# USBFTDI_I2C_V1.net
KiCad netlist of a schematic drawn in EAGLE
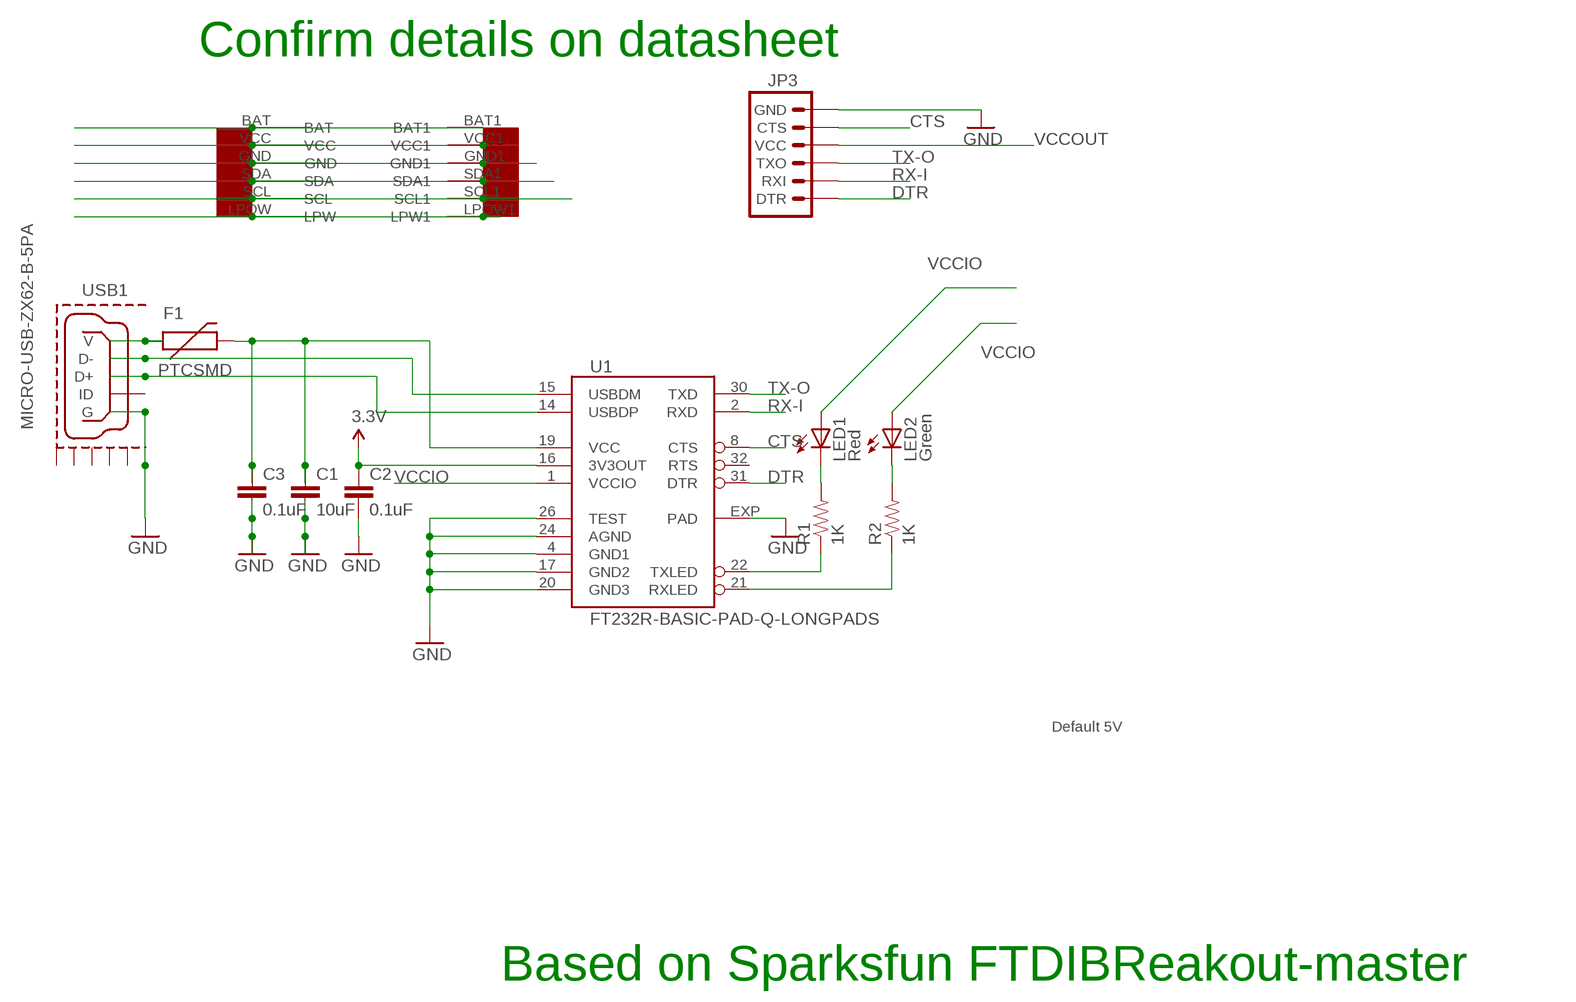
[diagram p0: schematic, sheet 1]

(export (version "E")
  (design (tool "Eeschema 10.0.6"))
  (components
    (comp (ref "C1")
      (value "10uF")
      (footprint "eagle-import:0402-CAP")
      (libsource (lib "eagle-import") (part "CAP-0402"))
    )
    (comp (ref "C2")
      (value "0.1uF")
      (footprint "eagle-import:0402-CAP")
      (libsource (lib "eagle-import") (part "CAP-0402"))
    )
    (comp (ref "C3")
      (value "0.1uF")
      (footprint "eagle-import:0402-CAP")
      (libsource (lib "eagle-import") (part "CAP-0402"))
    )
    (comp (ref "F1")
      (value "PTCSMD")
      (footprint "eagle-import:PTC-1206")
      (libsource (lib "eagle-import") (part "PTCSMD"))
    )
    (comp (ref "JP3")
      (value "ARDUINO_SERIAL_PROGRAMPTH")
      (footprint "eagle-import:1X06")
      (libsource (lib "eagle-import") (part "ARDUINO_SERIAL_PROGRAMPTH"))
    )
    (comp (ref "LED1")
      (value "Red")
      (footprint "eagle-import:LED-0603")
      (libsource (lib "eagle-import") (part "LED0603"))
    )
    (comp (ref "LED2")
      (value "Green")
      (footprint "eagle-import:LED-0603")
      (libsource (lib "eagle-import") (part "LED0603"))
    )
    (comp (ref "R1")
      (value "1K")
      (footprint "eagle-import:R0402")
      (libsource (lib "eagle-import") (part "RESISTOR-0402"))
    )
    (comp (ref "R2")
      (value "1K")
      (footprint "eagle-import:R0402")
      (libsource (lib "eagle-import") (part "RESISTOR-0402"))
    )
    (comp (ref "U$1")
      (value "EZ-I2CHEADERV1")
      (footprint "eagle-import:EZ-I2CHEADERV1")
      (libsource (lib "eagle-import") (part "EZ-I2CHEADERV1"))
    )
    (comp (ref "U1")
      (value "FT232R-BASIC-PAD-Q-LONGPADS")
      (footprint "eagle-import:QFN32-LONG")
      (libsource (lib "eagle-import") (part "FT232R-BASIC-PAD-Q-LONGPADS"))
    )
    (comp (ref "USB1")
      (value "MICRO-USB-ZX62-B-5PA")
      (footprint "eagle-import:ZX62-B-5PA")
      (libsource (lib "eagle-import") (part "MICRO-USB-ZX62-B-5PA"))
    )
  )
  (nets
    (net (code "1") (name "/CTS") (class "Default")
      (node (ref "JP3") (pin "5") (pinfunction "CTS_5") (pintype "passive"))
      (node (ref "U1") (pin "8") (pinfunction "CTS_8") (pintype "bidirectional"))
    )
    (net (code "2") (name "/DTR") (class "Default")
      (node (ref "JP3") (pin "1") (pinfunction "DTR_1") (pintype "passive"))
      (node (ref "U1") (pin "31") (pinfunction "DTR_31") (pintype "bidirectional"))
    )
    (net (code "3") (name "/GND1") (class "Default")
      (node (ref "USB1") (pin "GND@1") (pinfunction "GND1_GND@1") (pintype "power_in"))
    )
    (net (code "4") (name "/GND2") (class "Default")
      (node (ref "USB1") (pin "GND@2") (pinfunction "GND2_GND@2") (pintype "power_in"))
    )
    (net (code "5") (name "/GND3") (class "Default")
      (node (ref "USB1") (pin "GND@3") (pinfunction "GND3_GND@3") (pintype "power_in"))
    )
    (net (code "6") (name "/GND4") (class "Default")
      (node (ref "USB1") (pin "GND@4") (pinfunction "GND4_GND@4") (pintype "power_in"))
    )
    (net (code "7") (name "/GND5") (class "Default")
      (node (ref "USB1") (pin "GND@5") (pinfunction "GND5_GND@5") (pintype "power_in"))
    )
    (net (code "8") (name "/RX-I") (class "Default")
      (node (ref "JP3") (pin "2") (pinfunction "RXI_2") (pintype "passive"))
      (node (ref "U1") (pin "2") (pinfunction "RXD_2") (pintype "input"))
    )
    (net (code "9") (name "/TX-O") (class "Default")
      (node (ref "JP3") (pin "3") (pinfunction "TXO_3") (pintype "passive"))
      (node (ref "U1") (pin "30") (pinfunction "TXD_30") (pintype "output"))
    )
    (net (code "10") (name "/VCCIO") (class "Default")
      (node (ref "LED1") (pin "A") (pinfunction "A_A") (pintype "passive"))
      (node (ref "LED2") (pin "A") (pinfunction "A_A") (pintype "passive"))
      (node (ref "U1") (pin "1") (pinfunction "VCCIO_1") (pintype "power_in"))
    )
    (net (code "11") (name "/VCCOUT") (class "Default")
      (node (ref "JP3") (pin "4") (pinfunction "VCC_4") (pintype "passive"))
    )
    (net (code "12") (name "3.3V") (class "Default")
      (node (ref "C2") (pin "1") (pinfunction "1_1") (pintype "passive"))
      (node (ref "U$1") (pin "VCC") (pinfunction "VCC_VCC") (pintype "bidirectional"))
      (node (ref "U$1") (pin "VCC1") (pinfunction "VCC1_VCC1") (pintype "bidirectional"))
      (node (ref "U1") (pin "16") (pinfunction "3V3OUT_16") (pintype "output"))
    )
    (net (code "13") (name "GND") (class "Default")
      (node (ref "C1") (pin "2") (pinfunction "2_2") (pintype "passive"))
      (node (ref "C2") (pin "2") (pinfunction "2_2") (pintype "passive"))
      (node (ref "C3") (pin "2") (pinfunction "2_2") (pintype "passive"))
      (node (ref "JP3") (pin "6") (pinfunction "GND_6") (pintype "passive"))
      (node (ref "U$1") (pin "GND") (pinfunction "GND_GND") (pintype "bidirectional"))
      (node (ref "U$1") (pin "GND1") (pinfunction "GND1_GND1") (pintype "bidirectional"))
      (node (ref "U1") (pin "17") (pinfunction "GND2_17") (pintype "power_in"))
      (node (ref "U1") (pin "20") (pinfunction "GND3_20") (pintype "power_in"))
      (node (ref "U1") (pin "24") (pinfunction "AGND_24") (pintype "power_in"))
      (node (ref "U1") (pin "26") (pinfunction "TEST_26") (pintype "input"))
      (node (ref "U1") (pin "4") (pinfunction "GND1_4") (pintype "power_in"))
      (node (ref "U1") (pin "EXP") (pinfunction "PAD_EXP") (pintype "bidirectional"))
      (node (ref "USB1") (pin "5") (pinfunction "G_5") (pintype "input"))
      (node (ref "USB1") (pin "GND@6") (pinfunction "GND6_GND@6") (pintype "power_in"))
    )
    (net (code "14") (name "Net-(LED1-PadC)") (class "Default")
      (node (ref "LED1") (pin "C") (pinfunction "C_C") (pintype "passive"))
      (node (ref "R1") (pin "2") (pinfunction "2_2") (pintype "passive"))
    )
    (net (code "15") (name "Net-(LED2-PadC)") (class "Default")
      (node (ref "LED2") (pin "C") (pinfunction "C_C") (pintype "passive"))
      (node (ref "R2") (pin "2") (pinfunction "2_2") (pintype "passive"))
    )
    (net (code "16") (name "Net-(U$1-LPW)") (class "Default")
      (node (ref "U$1") (pin "LPOW") (pinfunction "LPW_LPOW") (pintype "bidirectional"))
      (node (ref "U$1") (pin "LPOW1") (pinfunction "LPW1_LPOW1") (pintype "bidirectional"))
    )
    (net (code "17") (name "Net-(U$1-PadBAT)") (class "Default")
      (node (ref "U$1") (pin "BAT") (pinfunction "BAT_BAT") (pintype "bidirectional"))
      (node (ref "U$1") (pin "BAT1") (pinfunction "BAT1_BAT1") (pintype "bidirectional"))
    )
    (net (code "18") (name "Net-(U$1-PadSCL)") (class "Default")
      (node (ref "U$1") (pin "SCL") (pinfunction "SCL_SCL") (pintype "bidirectional"))
      (node (ref "U$1") (pin "SCL1") (pinfunction "SCL1_SCL1") (pintype "bidirectional"))
    )
    (net (code "19") (name "Net-(U$1-PadSDA)") (class "Default")
      (node (ref "U$1") (pin "SDA") (pinfunction "SDA_SDA") (pintype "bidirectional"))
      (node (ref "U$1") (pin "SDA1") (pinfunction "SDA1_SDA1") (pintype "bidirectional"))
    )
    (net (code "20") (name "Net-(U1-RXLED)") (class "Default")
      (node (ref "R2") (pin "1") (pinfunction "1_1") (pintype "passive"))
      (node (ref "U1") (pin "21") (pinfunction "RXLED_21") (pintype "bidirectional"))
    )
    (net (code "21") (name "Net-(U1-TXLED)") (class "Default")
      (node (ref "R1") (pin "1") (pinfunction "1_1") (pintype "passive"))
      (node (ref "U1") (pin "22") (pinfunction "TXLED_22") (pintype "bidirectional"))
    )
    (net (code "22") (name "Net-(U1-USBDM)") (class "Default")
      (node (ref "U1") (pin "15") (pinfunction "USBDM_15") (pintype "bidirectional"))
      (node (ref "USB1") (pin "2") (pinfunction "D-_2") (pintype "input"))
    )
    (net (code "23") (name "Net-(U1-USBDP)") (class "Default")
      (node (ref "U1") (pin "14") (pinfunction "USBDP_14") (pintype "bidirectional"))
      (node (ref "USB1") (pin "3") (pinfunction "D+_3") (pintype "input"))
    )
    (net (code "24") (name "Net-(U1-VCC)") (class "Default")
      (node (ref "C1") (pin "1") (pinfunction "1_1") (pintype "passive"))
      (node (ref "C3") (pin "1") (pinfunction "1_1") (pintype "passive"))
      (node (ref "F1") (pin "2") (pinfunction "2_2") (pintype "bidirectional"))
      (node (ref "U1") (pin "19") (pinfunction "VCC_19") (pintype "power_in"))
    )
    (net (code "25") (name "Net-(USB1-V)") (class "Default")
      (node (ref "F1") (pin "1") (pinfunction "1_1") (pintype "bidirectional"))
      (node (ref "USB1") (pin "1") (pinfunction "V_1") (pintype "input"))
    )
    (net (code "26") (name "unconnected-(U1-RTS-Pad32)") (class "Default")
      (node (ref "U1") (pin "32") (pinfunction "RTS_32") (pintype "bidirectional"))
    )
    (net (code "27") (name "unconnected-(USB1-ID-Pad4)") (class "Default")
      (node (ref "USB1") (pin "4") (pinfunction "ID_4") (pintype "input"))
    )
  )
)
